# cube_board.net
KiCad netlist of a schematic drawn in EAGLE
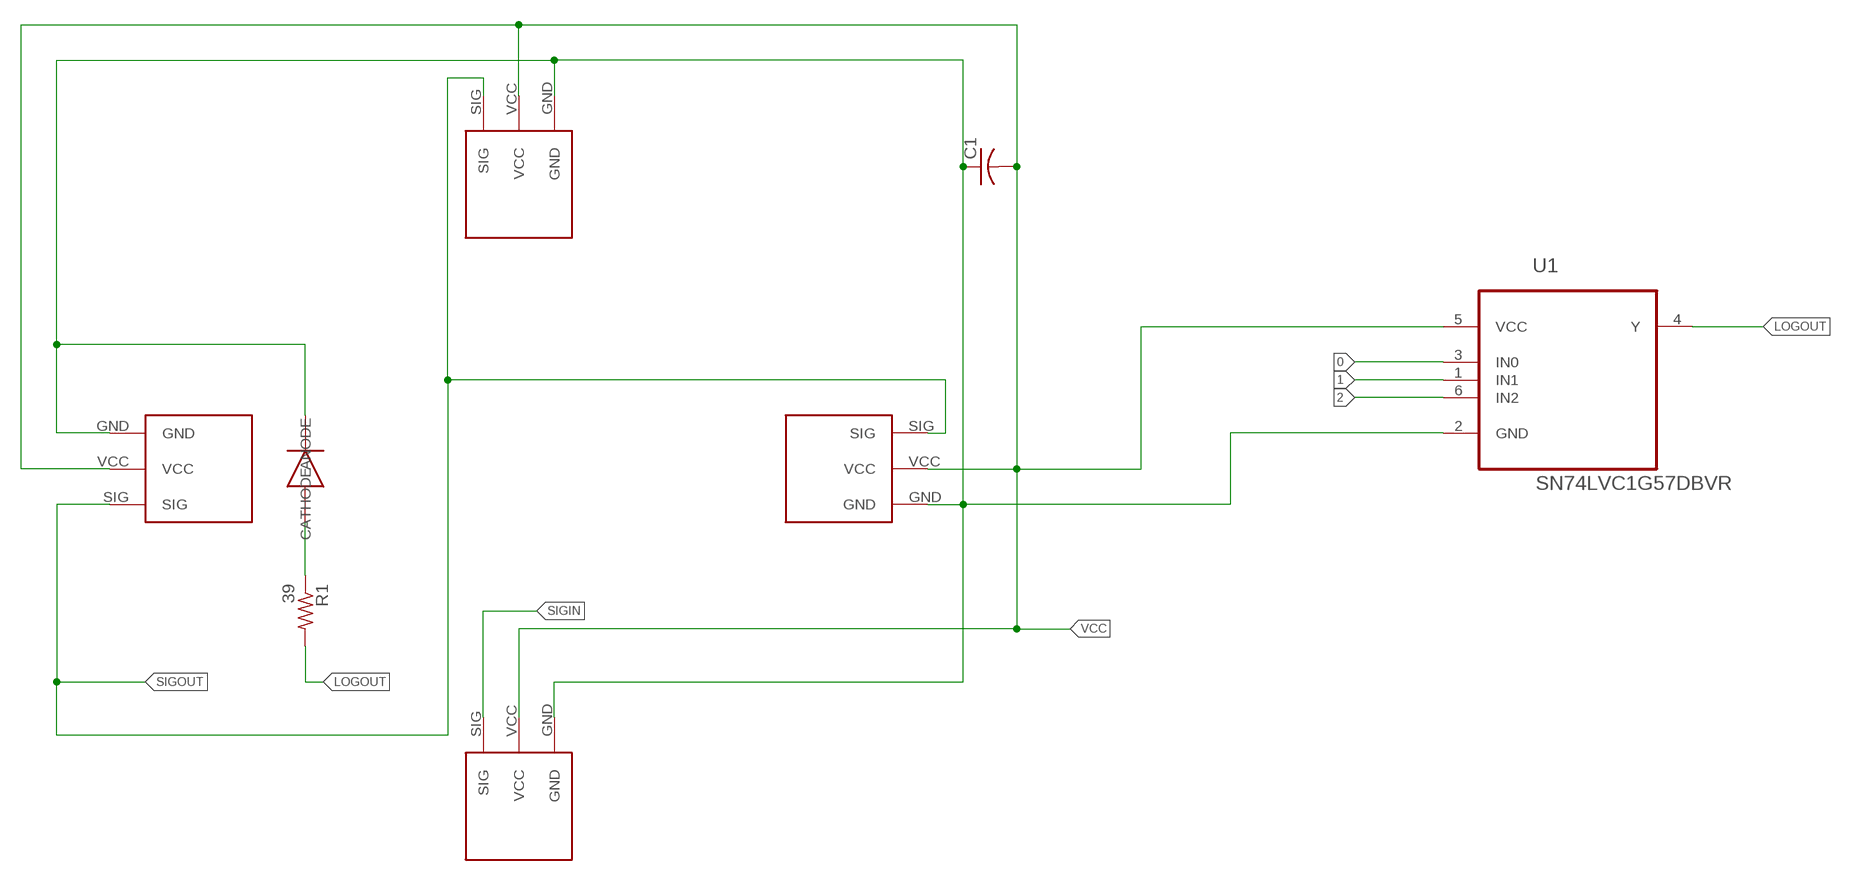
[diagram p0: schematic, sheet 1]

(export (version "E")
  (design (tool "Eeschema 10.0.6"))
  (components
    (comp (ref "C1")
      (value "C-USC0805")
      (footprint "eagle-import:C0805")
      (libsource (lib "eagle-import") (part "C-USC0805"))
    )
    (comp (ref "LED")
      (value "SMD_LED")
      (footprint "eagle-import:SMD_LED")
      (libsource (lib "eagle-import") (part "SMD_LED"))
    )
    (comp (ref "R1")
      (value "39")
      (footprint "eagle-import:M1206")
      (libsource (lib "eagle-import") (part "R-US_M1206"))
    )
    (comp (ref "U$2")
      (value "CUBE_CONNECTOR")
      (footprint "eagle-import:CUBE_CONNECTOR")
      (libsource (lib "eagle-import") (part "CUBE_CONNECTOR"))
    )
    (comp (ref "U$3")
      (value "CUBE_CONNECTOR")
      (footprint "eagle-import:CUBE_CONNECTOR")
      (libsource (lib "eagle-import") (part "CUBE_CONNECTOR"))
    )
    (comp (ref "U$4")
      (value "CUBE_CONNECTOR")
      (footprint "eagle-import:CUBE_CONNECTOR")
      (libsource (lib "eagle-import") (part "CUBE_CONNECTOR"))
    )
    (comp (ref "U$5")
      (value "CUBE_CONNECTOR")
      (footprint "eagle-import:CUBE_CONNECTOR")
      (libsource (lib "eagle-import") (part "CUBE_CONNECTOR"))
    )
    (comp (ref "U1")
      (value "SN74LVC1G57DBVR")
      (footprint "eagle-import:SOT95P280X145-6N")
      (libsource (lib "eagle-import") (part "SN74LVC1G57DBVR"))
    )
  )
  (nets
    (net (code "1") (name "0") (class "Default")
      (node (ref "U1") (pin "3") (pinfunction "IN0_3") (pintype "input"))
    )
    (net (code "2") (name "1") (class "Default")
      (node (ref "U1") (pin "1") (pinfunction "IN1_1") (pintype "input"))
    )
    (net (code "3") (name "2") (class "Default")
      (node (ref "U1") (pin "6") (pinfunction "IN2_6") (pintype "input"))
    )
    (net (code "4") (name "LOGOUT") (class "Default")
      (node (ref "R1") (pin "2") (pinfunction "2_2") (pintype "passive"))
      (node (ref "U1") (pin "4") (pinfunction "Y_4") (pintype "output"))
    )
    (net (code "5") (name "Net-(LED-PadANODE)") (class "Default")
      (node (ref "LED") (pin "ANODE") (pinfunction "ANODE_ANODE") (pintype "bidirectional"))
      (node (ref "R1") (pin "1") (pinfunction "1_1") (pintype "passive"))
    )
    (net (code "6") (name "Net-(U1-GND)") (class "Default")
      (node (ref "C1") (pin "1") (pinfunction "1_1") (pintype "passive"))
      (node (ref "LED") (pin "CATHODE") (pinfunction "CATHODE_CATHODE") (pintype "bidirectional"))
      (node (ref "U$2") (pin "GND") (pinfunction "GND_GND") (pintype "bidirectional"))
      (node (ref "U$3") (pin "GND") (pinfunction "GND_GND") (pintype "bidirectional"))
      (node (ref "U$4") (pin "GND") (pinfunction "GND_GND") (pintype "bidirectional"))
      (node (ref "U$5") (pin "GND") (pinfunction "GND_GND") (pintype "bidirectional"))
      (node (ref "U1") (pin "2") (pinfunction "GND_2") (pintype "passive"))
    )
    (net (code "7") (name "SIGIN") (class "Default")
      (node (ref "U$2") (pin "SIG") (pinfunction "SIG_SIG") (pintype "bidirectional"))
    )
    (net (code "8") (name "SIGOUT") (class "Default")
      (node (ref "U$3") (pin "SIG") (pinfunction "SIG_SIG") (pintype "bidirectional"))
      (node (ref "U$4") (pin "SIG") (pinfunction "SIG_SIG") (pintype "bidirectional"))
      (node (ref "U$5") (pin "SIG") (pinfunction "SIG_SIG") (pintype "bidirectional"))
    )
    (net (code "9") (name "VCC") (class "Default")
      (node (ref "C1") (pin "2") (pinfunction "2_2") (pintype "passive"))
      (node (ref "U$2") (pin "VCC") (pinfunction "VCC_VCC") (pintype "bidirectional"))
      (node (ref "U$3") (pin "VCC") (pinfunction "VCC_VCC") (pintype "bidirectional"))
      (node (ref "U$4") (pin "VCC") (pinfunction "VCC_VCC") (pintype "bidirectional"))
      (node (ref "U$5") (pin "VCC") (pinfunction "VCC_VCC") (pintype "bidirectional"))
      (node (ref "U1") (pin "5") (pinfunction "VCC_5") (pintype "power_in"))
    )
  )
)
